# USB_DLT.net
KiCad netlist of a schematic drawn in EAGLE
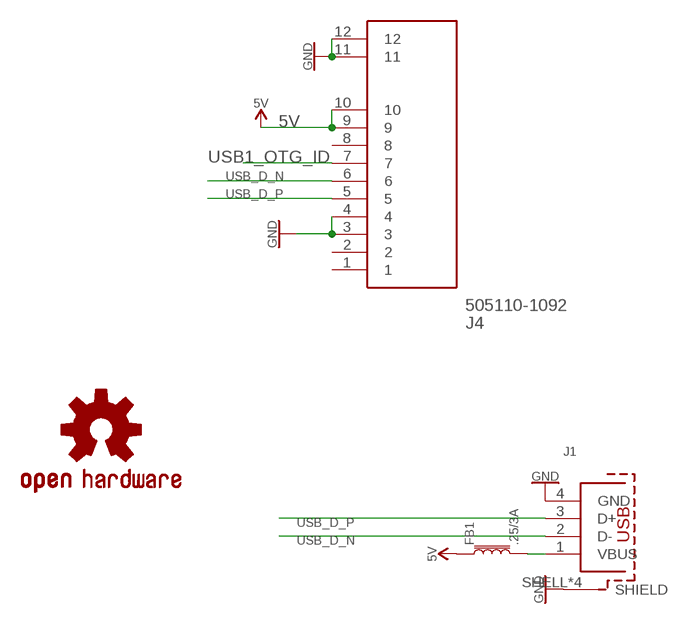
[diagram p0: schematic, sheet 1]

(export (version "E")
  (design (tool "Eeschema 10.0.6"))
  (components
    (comp (ref "FB1")
      (value ".25/3A")
      (footprint "eagle-import:0603")
      (libsource (lib "eagle-import") (part "FERRITE_BEAD-0603"))
    )
    (comp (ref "J1")
      (value "629104190121")
      (footprint "eagle-import:629104190121")
      (libsource (lib "eagle-import") (part "629104190121"))
    )
    (comp (ref "J4")
      (value "505110-1092")
      (footprint "eagle-import:5051101092")
      (fields (field (name "MOUSER_PART_NUMBER") "538-505110-1092"))
      (libsource (lib "eagle-import") (part "505110-1092"))
    )
    (comp (ref "LOGO1")
      (value "OSHW-LOGOS-COPPER")
      (footprint "eagle-import:OSHW-LOGO-S_COPPER")
      (libsource (lib "eagle-import") (part "OSHW-LOGOS-COPPER"))
    )
  )
  (nets
    (net (code "1") (name "/USB1_OTG_ID") (class "Default")
      (node (ref "J4") (pin "7") (pinfunction "7_7") (pintype "bidirectional"))
    )
    (net (code "2") (name "/USB_D_N") (class "Default")
      (node (ref "J1") (pin "2") (pinfunction "D-_2") (pintype "bidirectional"))
      (node (ref "J4") (pin "6") (pinfunction "6_6") (pintype "bidirectional"))
    )
    (net (code "3") (name "/USB_D_P") (class "Default")
      (node (ref "J1") (pin "3") (pinfunction "D+_3") (pintype "bidirectional"))
      (node (ref "J4") (pin "5") (pinfunction "5_5") (pintype "bidirectional"))
    )
    (net (code "4") (name "5V") (class "Default")
      (node (ref "FB1") (pin "1") (pinfunction "1_1") (pintype "passive"))
      (node (ref "J4") (pin "10") (pinfunction "10_10") (pintype "bidirectional"))
      (node (ref "J4") (pin "9") (pinfunction "9_9") (pintype "bidirectional"))
    )
    (net (code "5") (name "GND") (class "Default")
      (node (ref "J1") (pin "4") (pinfunction "GND_4") (pintype "bidirectional"))
      (node (ref "J1") (pin "SHELL") (pinfunction "SHIELD_SHELL") (pintype "bidirectional"))
      (node (ref "J1") (pin "SHELL1") (pinfunction "SHIELD_SHELL1") (pintype "bidirectional"))
      (node (ref "J1") (pin "SHELL2") (pinfunction "SHIELD_SHELL2") (pintype "bidirectional"))
      (node (ref "J1") (pin "SHELL3") (pinfunction "SHIELD_SHELL3") (pintype "bidirectional"))
      (node (ref "J4") (pin "11") (pinfunction "11_11") (pintype "bidirectional"))
      (node (ref "J4") (pin "12") (pinfunction "12_12") (pintype "bidirectional"))
      (node (ref "J4") (pin "3") (pinfunction "3_3") (pintype "bidirectional"))
      (node (ref "J4") (pin "4") (pinfunction "4_4") (pintype "bidirectional"))
    )
    (net (code "6") (name "Net-(J1-VBUS)") (class "Default")
      (node (ref "FB1") (pin "2") (pinfunction "2_2") (pintype "passive"))
      (node (ref "J1") (pin "1") (pinfunction "VBUS_1") (pintype "bidirectional"))
    )
    (net (code "7") (name "unconnected-(J4-Pad1)") (class "Default")
      (node (ref "J4") (pin "1") (pinfunction "1_1") (pintype "bidirectional"))
    )
    (net (code "8") (name "unconnected-(J4-Pad2)") (class "Default")
      (node (ref "J4") (pin "2") (pinfunction "2_2") (pintype "bidirectional"))
    )
    (net (code "9") (name "unconnected-(J4-Pad8)") (class "Default")
      (node (ref "J4") (pin "8") (pinfunction "8_8") (pintype "bidirectional"))
    )
  )
)
